# bancada_hx711.net
KiCad netlist of a schematic drawn in EAGLE
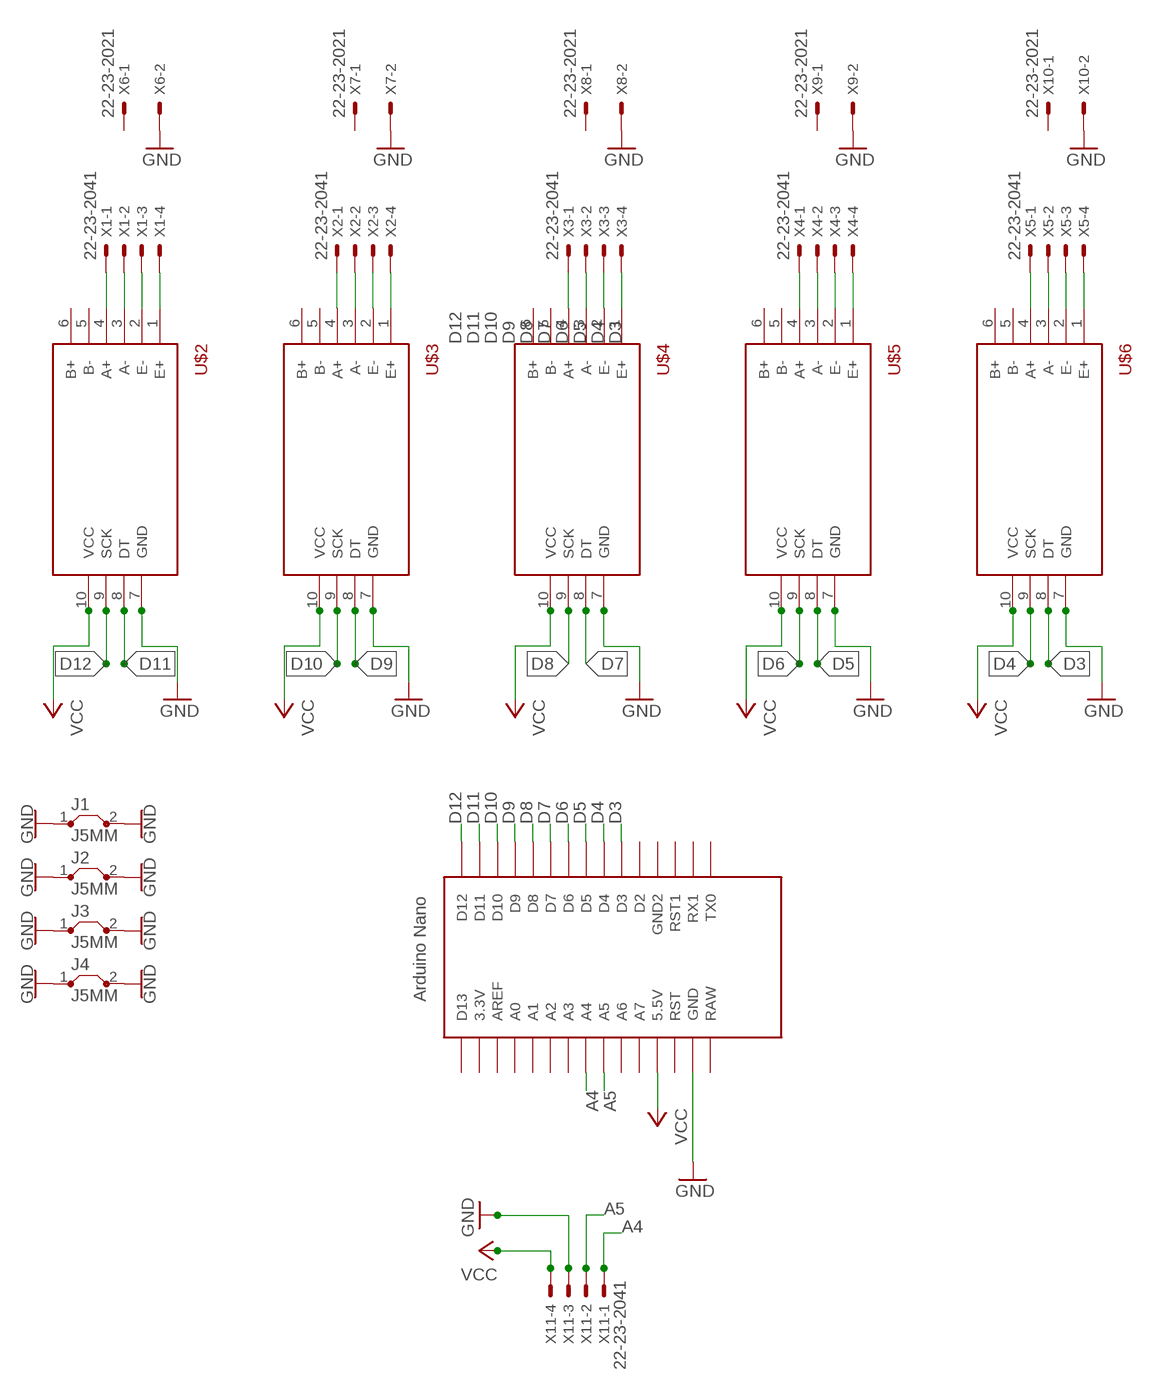
[diagram p0: schematic, sheet 1]

(export (version "E")
  (design (tool "Eeschema 10.0.6"))
  (components
    (comp (ref "J1")
      (value "J5MM")
      (footprint "eagle-import:05")
      (libsource (lib "eagle-import") (part "J5MM"))
    )
    (comp (ref "J2")
      (value "J5MM")
      (footprint "eagle-import:05")
      (libsource (lib "eagle-import") (part "J5MM"))
    )
    (comp (ref "J3")
      (value "J5MM")
      (footprint "eagle-import:05")
      (libsource (lib "eagle-import") (part "J5MM"))
    )
    (comp (ref "J4")
      (value "J5MM")
      (footprint "eagle-import:05")
      (libsource (lib "eagle-import") (part "J5MM"))
    )
    (comp (ref "U$1")
      (value "NANO")
      (footprint "eagle-import:NANO")
      (libsource (lib "eagle-import") (part "NANO"))
    )
    (comp (ref "U$2")
      (value "HX711-1")
      (footprint "eagle-import:HX711-1")
      (libsource (lib "eagle-import") (part "HX711-1"))
    )
    (comp (ref "U$3")
      (value "HX711-1")
      (footprint "eagle-import:HX711-1")
      (libsource (lib "eagle-import") (part "HX711-1"))
    )
    (comp (ref "U$4")
      (value "HX711-1")
      (footprint "eagle-import:HX711-1")
      (libsource (lib "eagle-import") (part "HX711-1"))
    )
    (comp (ref "U$5")
      (value "HX711-1")
      (footprint "eagle-import:HX711-1")
      (libsource (lib "eagle-import") (part "HX711-1"))
    )
    (comp (ref "U$6")
      (value "HX711-1")
      (footprint "eagle-import:HX711-1")
      (libsource (lib "eagle-import") (part "HX711-1"))
    )
    (comp (ref "X1")
      (value "22-23-2041")
      (footprint "eagle-import:22-23-2041")
      (fields (field (name "MF") "MOLEX"))
      (libsource (lib "eagle-import") (part "22-23-2041"))
    )
    (comp (ref "X2")
      (value "22-23-2041")
      (footprint "eagle-import:22-23-2041")
      (fields (field (name "MF") "MOLEX"))
      (libsource (lib "eagle-import") (part "22-23-2041"))
    )
    (comp (ref "X3")
      (value "22-23-2041")
      (footprint "eagle-import:22-23-2041")
      (fields (field (name "MF") "MOLEX"))
      (libsource (lib "eagle-import") (part "22-23-2041"))
    )
    (comp (ref "X4")
      (value "22-23-2041")
      (footprint "eagle-import:22-23-2041")
      (fields (field (name "MF") "MOLEX"))
      (libsource (lib "eagle-import") (part "22-23-2041"))
    )
    (comp (ref "X5")
      (value "22-23-2041")
      (footprint "eagle-import:22-23-2041")
      (fields (field (name "MF") "MOLEX"))
      (libsource (lib "eagle-import") (part "22-23-2041"))
    )
    (comp (ref "X6")
      (value "22-23-2021")
      (footprint "eagle-import:22-23-2021")
      (fields (field (name "MF") "MOLEX"))
      (libsource (lib "eagle-import") (part "22-23-2021"))
    )
    (comp (ref "X7")
      (value "22-23-2021")
      (footprint "eagle-import:22-23-2021")
      (fields (field (name "MF") "MOLEX"))
      (libsource (lib "eagle-import") (part "22-23-2021"))
    )
    (comp (ref "X8")
      (value "22-23-2021")
      (footprint "eagle-import:22-23-2021")
      (fields (field (name "MF") "MOLEX"))
      (libsource (lib "eagle-import") (part "22-23-2021"))
    )
    (comp (ref "X9")
      (value "22-23-2021")
      (footprint "eagle-import:22-23-2021")
      (fields (field (name "MF") "MOLEX"))
      (libsource (lib "eagle-import") (part "22-23-2021"))
    )
    (comp (ref "X10")
      (value "22-23-2021")
      (footprint "eagle-import:22-23-2021")
      (fields (field (name "MF") "MOLEX"))
      (libsource (lib "eagle-import") (part "22-23-2021"))
    )
    (comp (ref "X11")
      (value "22-23-2041")
      (footprint "eagle-import:22-23-2041")
      (fields (field (name "MF") "MOLEX"))
      (libsource (lib "eagle-import") (part "22-23-2041"))
    )
  )
  (nets
    (net (code "1") (name "/A4") (class "Default")
      (node (ref "U$1") (pin "A4") (pinfunction "A4_A4") (pintype "bidirectional"))
      (node (ref "X11") (pin "1") (pinfunction "S_1") (pintype "passive"))
    )
    (net (code "2") (name "/A5") (class "Default")
      (node (ref "U$1") (pin "A5") (pinfunction "A5_A5") (pintype "bidirectional"))
      (node (ref "X11") (pin "2") (pinfunction "S_2") (pintype "passive"))
    )
    (net (code "3") (name "D3") (class "Default")
      (node (ref "U$1") (pin "D3") (pinfunction "D3_D3") (pintype "bidirectional"))
      (node (ref "U$6") (pin "8") (pinfunction "DT_8") (pintype "bidirectional"))
    )
    (net (code "4") (name "D4") (class "Default")
      (node (ref "U$1") (pin "D4") (pinfunction "D4_D4") (pintype "bidirectional"))
      (node (ref "U$6") (pin "9") (pinfunction "SCK_9") (pintype "bidirectional"))
    )
    (net (code "5") (name "D5") (class "Default")
      (node (ref "U$1") (pin "D5") (pinfunction "D5_D5") (pintype "bidirectional"))
      (node (ref "U$5") (pin "8") (pinfunction "DT_8") (pintype "bidirectional"))
    )
    (net (code "6") (name "D6") (class "Default")
      (node (ref "U$1") (pin "D6") (pinfunction "D6_D6") (pintype "bidirectional"))
      (node (ref "U$5") (pin "9") (pinfunction "SCK_9") (pintype "bidirectional"))
    )
    (net (code "7") (name "D7") (class "Default")
      (node (ref "U$1") (pin "D7") (pinfunction "D7_D7") (pintype "bidirectional"))
      (node (ref "U$4") (pin "8") (pinfunction "DT_8") (pintype "bidirectional"))
    )
    (net (code "8") (name "D8") (class "Default")
      (node (ref "U$1") (pin "D8") (pinfunction "D8_D8") (pintype "bidirectional"))
      (node (ref "U$4") (pin "9") (pinfunction "SCK_9") (pintype "bidirectional"))
    )
    (net (code "9") (name "D9") (class "Default")
      (node (ref "U$1") (pin "D9") (pinfunction "D9_D9") (pintype "bidirectional"))
      (node (ref "U$3") (pin "8") (pinfunction "DT_8") (pintype "bidirectional"))
    )
    (net (code "10") (name "D10") (class "Default")
      (node (ref "U$1") (pin "D10") (pinfunction "D10_D10") (pintype "bidirectional"))
      (node (ref "U$3") (pin "9") (pinfunction "SCK_9") (pintype "bidirectional"))
    )
    (net (code "11") (name "D11") (class "Default")
      (node (ref "U$1") (pin "D11") (pinfunction "D11_D11") (pintype "bidirectional"))
      (node (ref "U$2") (pin "8") (pinfunction "DT_8") (pintype "bidirectional"))
    )
    (net (code "12") (name "D12") (class "Default")
      (node (ref "U$1") (pin "D12") (pinfunction "D12_D12") (pintype "bidirectional"))
      (node (ref "U$2") (pin "9") (pinfunction "SCK_9") (pintype "bidirectional"))
    )
    (net (code "13") (name "GND") (class "Default")
      (node (ref "J1") (pin "1") (pinfunction "1_1") (pintype "passive"))
      (node (ref "J1") (pin "2") (pinfunction "2_2") (pintype "passive"))
      (node (ref "J2") (pin "1") (pinfunction "1_1") (pintype "passive"))
      (node (ref "J2") (pin "2") (pinfunction "2_2") (pintype "passive"))
      (node (ref "J3") (pin "1") (pinfunction "1_1") (pintype "passive"))
      (node (ref "J3") (pin "2") (pinfunction "2_2") (pintype "passive"))
      (node (ref "J4") (pin "1") (pinfunction "1_1") (pintype "passive"))
      (node (ref "J4") (pin "2") (pinfunction "2_2") (pintype "passive"))
      (node (ref "U$1") (pin "GND") (pinfunction "GND_GND") (pintype "bidirectional"))
      (node (ref "U$2") (pin "7") (pinfunction "GND_7") (pintype "bidirectional"))
      (node (ref "U$3") (pin "7") (pinfunction "GND_7") (pintype "bidirectional"))
      (node (ref "U$4") (pin "7") (pinfunction "GND_7") (pintype "bidirectional"))
      (node (ref "U$5") (pin "7") (pinfunction "GND_7") (pintype "bidirectional"))
      (node (ref "U$6") (pin "7") (pinfunction "GND_7") (pintype "bidirectional"))
      (node (ref "X10") (pin "2") (pinfunction "S_2") (pintype "passive"))
      (node (ref "X11") (pin "3") (pinfunction "S_3") (pintype "passive"))
      (node (ref "X6") (pin "2") (pinfunction "S_2") (pintype "passive"))
      (node (ref "X7") (pin "2") (pinfunction "S_2") (pintype "passive"))
      (node (ref "X8") (pin "2") (pinfunction "S_2") (pintype "passive"))
      (node (ref "X9") (pin "2") (pinfunction "S_2") (pintype "passive"))
    )
    (net (code "14") (name "Net-(U$2-A+)") (class "Default")
      (node (ref "U$2") (pin "4") (pinfunction "A+_4") (pintype "bidirectional"))
      (node (ref "X1") (pin "1") (pinfunction "S_1") (pintype "passive"))
    )
    (net (code "15") (name "Net-(U$2-A-)") (class "Default")
      (node (ref "U$2") (pin "3") (pinfunction "A-_3") (pintype "bidirectional"))
      (node (ref "X1") (pin "2") (pinfunction "S_2") (pintype "passive"))
    )
    (net (code "16") (name "Net-(U$2-E+)") (class "Default")
      (node (ref "U$2") (pin "1") (pinfunction "E+_1") (pintype "bidirectional"))
      (node (ref "X1") (pin "4") (pinfunction "S_4") (pintype "passive"))
    )
    (net (code "17") (name "Net-(U$2-E-)") (class "Default")
      (node (ref "U$2") (pin "2") (pinfunction "E-_2") (pintype "bidirectional"))
      (node (ref "X1") (pin "3") (pinfunction "S_3") (pintype "passive"))
    )
    (net (code "18") (name "Net-(U$3-A+)") (class "Default")
      (node (ref "U$3") (pin "4") (pinfunction "A+_4") (pintype "bidirectional"))
      (node (ref "X2") (pin "1") (pinfunction "S_1") (pintype "passive"))
    )
    (net (code "19") (name "Net-(U$3-A-)") (class "Default")
      (node (ref "U$3") (pin "3") (pinfunction "A-_3") (pintype "bidirectional"))
      (node (ref "X2") (pin "2") (pinfunction "S_2") (pintype "passive"))
    )
    (net (code "20") (name "Net-(U$3-E+)") (class "Default")
      (node (ref "U$3") (pin "1") (pinfunction "E+_1") (pintype "bidirectional"))
      (node (ref "X2") (pin "4") (pinfunction "S_4") (pintype "passive"))
    )
    (net (code "21") (name "Net-(U$3-E-)") (class "Default")
      (node (ref "U$3") (pin "2") (pinfunction "E-_2") (pintype "bidirectional"))
      (node (ref "X2") (pin "3") (pinfunction "S_3") (pintype "passive"))
    )
    (net (code "22") (name "Net-(U$4-A+)") (class "Default")
      (node (ref "U$4") (pin "4") (pinfunction "A+_4") (pintype "bidirectional"))
      (node (ref "X3") (pin "1") (pinfunction "S_1") (pintype "passive"))
    )
    (net (code "23") (name "Net-(U$4-A-)") (class "Default")
      (node (ref "U$4") (pin "3") (pinfunction "A-_3") (pintype "bidirectional"))
      (node (ref "X3") (pin "2") (pinfunction "S_2") (pintype "passive"))
    )
    (net (code "24") (name "Net-(U$4-E+)") (class "Default")
      (node (ref "U$4") (pin "1") (pinfunction "E+_1") (pintype "bidirectional"))
      (node (ref "X3") (pin "4") (pinfunction "S_4") (pintype "passive"))
    )
    (net (code "25") (name "Net-(U$4-E-)") (class "Default")
      (node (ref "U$4") (pin "2") (pinfunction "E-_2") (pintype "bidirectional"))
      (node (ref "X3") (pin "3") (pinfunction "S_3") (pintype "passive"))
    )
    (net (code "26") (name "Net-(U$5-A+)") (class "Default")
      (node (ref "U$5") (pin "4") (pinfunction "A+_4") (pintype "bidirectional"))
      (node (ref "X4") (pin "1") (pinfunction "S_1") (pintype "passive"))
    )
    (net (code "27") (name "Net-(U$5-A-)") (class "Default")
      (node (ref "U$5") (pin "3") (pinfunction "A-_3") (pintype "bidirectional"))
      (node (ref "X4") (pin "2") (pinfunction "S_2") (pintype "passive"))
    )
    (net (code "28") (name "Net-(U$5-E+)") (class "Default")
      (node (ref "U$5") (pin "1") (pinfunction "E+_1") (pintype "bidirectional"))
      (node (ref "X4") (pin "4") (pinfunction "S_4") (pintype "passive"))
    )
    (net (code "29") (name "Net-(U$5-E-)") (class "Default")
      (node (ref "U$5") (pin "2") (pinfunction "E-_2") (pintype "bidirectional"))
      (node (ref "X4") (pin "3") (pinfunction "S_3") (pintype "passive"))
    )
    (net (code "30") (name "Net-(U$6-A+)") (class "Default")
      (node (ref "U$6") (pin "4") (pinfunction "A+_4") (pintype "bidirectional"))
      (node (ref "X5") (pin "1") (pinfunction "S_1") (pintype "passive"))
    )
    (net (code "31") (name "Net-(U$6-A-)") (class "Default")
      (node (ref "U$6") (pin "3") (pinfunction "A-_3") (pintype "bidirectional"))
      (node (ref "X5") (pin "2") (pinfunction "S_2") (pintype "passive"))
    )
    (net (code "32") (name "Net-(U$6-E+)") (class "Default")
      (node (ref "U$6") (pin "1") (pinfunction "E+_1") (pintype "bidirectional"))
      (node (ref "X5") (pin "4") (pinfunction "S_4") (pintype "passive"))
    )
    (net (code "33") (name "Net-(U$6-E-)") (class "Default")
      (node (ref "U$6") (pin "2") (pinfunction "E-_2") (pintype "bidirectional"))
      (node (ref "X5") (pin "3") (pinfunction "S_3") (pintype "passive"))
    )
    (net (code "34") (name "VCC") (class "Default")
      (node (ref "U$1") (pin "5V") (pinfunction "5.5V_5V") (pintype "bidirectional"))
      (node (ref "U$2") (pin "10") (pinfunction "VCC_10") (pintype "bidirectional"))
      (node (ref "U$3") (pin "10") (pinfunction "VCC_10") (pintype "bidirectional"))
      (node (ref "U$4") (pin "10") (pinfunction "VCC_10") (pintype "bidirectional"))
      (node (ref "U$5") (pin "10") (pinfunction "VCC_10") (pintype "bidirectional"))
      (node (ref "U$6") (pin "10") (pinfunction "VCC_10") (pintype "bidirectional"))
      (node (ref "X11") (pin "4") (pinfunction "S_4") (pintype "passive"))
    )
    (net (code "35") (name "unconnected-(U$1-GND2-PadGND1)") (class "Default")
      (node (ref "U$1") (pin "GND1") (pinfunction "GND2_GND1") (pintype "bidirectional"))
    )
    (net (code "36") (name "unconnected-(U$1-Pad3.3V)") (class "Default")
      (node (ref "U$1") (pin "3.3V") (pinfunction "3.3V_3.3V") (pintype "bidirectional"))
    )
    (net (code "37") (name "unconnected-(U$1-PadA0)") (class "Default")
      (node (ref "U$1") (pin "A0") (pinfunction "A0_A0") (pintype "bidirectional"))
    )
    (net (code "38") (name "unconnected-(U$1-PadA1)") (class "Default")
      (node (ref "U$1") (pin "A1") (pinfunction "A1_A1") (pintype "bidirectional"))
    )
    (net (code "39") (name "unconnected-(U$1-PadA2)") (class "Default")
      (node (ref "U$1") (pin "A2") (pinfunction "A2_A2") (pintype "bidirectional"))
    )
    (net (code "40") (name "unconnected-(U$1-PadA3)") (class "Default")
      (node (ref "U$1") (pin "A3") (pinfunction "A3_A3") (pintype "bidirectional"))
    )
    (net (code "41") (name "unconnected-(U$1-PadA6)") (class "Default")
      (node (ref "U$1") (pin "A6") (pinfunction "A6_A6") (pintype "bidirectional"))
    )
    (net (code "42") (name "unconnected-(U$1-PadA7)") (class "Default")
      (node (ref "U$1") (pin "A7") (pinfunction "A7_A7") (pintype "bidirectional"))
    )
    (net (code "43") (name "unconnected-(U$1-PadAREF)") (class "Default")
      (node (ref "U$1") (pin "AREF") (pinfunction "AREF_AREF") (pintype "bidirectional"))
    )
    (net (code "44") (name "unconnected-(U$1-PadD2)") (class "Default")
      (node (ref "U$1") (pin "D2") (pinfunction "D2_D2") (pintype "bidirectional"))
    )
    (net (code "45") (name "unconnected-(U$1-PadD13)") (class "Default")
      (node (ref "U$1") (pin "D13") (pinfunction "D13_D13") (pintype "bidirectional"))
    )
    (net (code "46") (name "unconnected-(U$1-PadICSP1)") (class "Default")
      (node (ref "U$1") (pin "ICSP1") (pinfunction "ICSP1_ICSP1") (pintype "bidirectional"))
    )
    (net (code "47") (name "unconnected-(U$1-PadICSP2)") (class "Default")
      (node (ref "U$1") (pin "ICSP2") (pinfunction "ICSP2_ICSP2") (pintype "bidirectional"))
    )
    (net (code "48") (name "unconnected-(U$1-PadICSP3)") (class "Default")
      (node (ref "U$1") (pin "ICSP3") (pinfunction "ICSP3_ICSP3") (pintype "bidirectional"))
    )
    (net (code "49") (name "unconnected-(U$1-PadICSP4)") (class "Default")
      (node (ref "U$1") (pin "ICSP4") (pinfunction "ICSP4_ICSP4") (pintype "bidirectional"))
    )
    (net (code "50") (name "unconnected-(U$1-PadICSP5)") (class "Default")
      (node (ref "U$1") (pin "ICSP5") (pinfunction "ICSP5_ICSP5") (pintype "bidirectional"))
    )
    (net (code "51") (name "unconnected-(U$1-PadICSP6)") (class "Default")
      (node (ref "U$1") (pin "ICSP6") (pinfunction "ICSP6_ICSP6") (pintype "bidirectional"))
    )
    (net (code "52") (name "unconnected-(U$1-PadRAW)") (class "Default")
      (node (ref "U$1") (pin "RAW") (pinfunction "RAW_RAW") (pintype "bidirectional"))
    )
    (net (code "53") (name "unconnected-(U$1-PadRST)") (class "Default")
      (node (ref "U$1") (pin "RST") (pinfunction "RST_RST") (pintype "bidirectional"))
    )
    (net (code "54") (name "unconnected-(U$1-PadRST1)") (class "Default")
      (node (ref "U$1") (pin "RST1") (pinfunction "RST1_RST1") (pintype "bidirectional"))
    )
    (net (code "55") (name "unconnected-(U$1-PadRX1)") (class "Default")
      (node (ref "U$1") (pin "RX1") (pinfunction "RX1_RX1") (pintype "bidirectional"))
    )
    (net (code "56") (name "unconnected-(U$1-PadTX0)") (class "Default")
      (node (ref "U$1") (pin "TX0") (pinfunction "TX0_TX0") (pintype "bidirectional"))
    )
    (net (code "57") (name "unconnected-(U$2-B+-Pad6)") (class "Default")
      (node (ref "U$2") (pin "6") (pinfunction "B+_6") (pintype "bidirectional"))
    )
    (net (code "58") (name "unconnected-(U$2-B--Pad5)") (class "Default")
      (node (ref "U$2") (pin "5") (pinfunction "B-_5") (pintype "bidirectional"))
    )
    (net (code "59") (name "unconnected-(U$3-B+-Pad6)") (class "Default")
      (node (ref "U$3") (pin "6") (pinfunction "B+_6") (pintype "bidirectional"))
    )
    (net (code "60") (name "unconnected-(U$3-B--Pad5)") (class "Default")
      (node (ref "U$3") (pin "5") (pinfunction "B-_5") (pintype "bidirectional"))
    )
    (net (code "61") (name "unconnected-(U$4-B+-Pad6)") (class "Default")
      (node (ref "U$4") (pin "6") (pinfunction "B+_6") (pintype "bidirectional"))
    )
    (net (code "62") (name "unconnected-(U$4-B--Pad5)") (class "Default")
      (node (ref "U$4") (pin "5") (pinfunction "B-_5") (pintype "bidirectional"))
    )
    (net (code "63") (name "unconnected-(U$5-B+-Pad6)") (class "Default")
      (node (ref "U$5") (pin "6") (pinfunction "B+_6") (pintype "bidirectional"))
    )
    (net (code "64") (name "unconnected-(U$5-B--Pad5)") (class "Default")
      (node (ref "U$5") (pin "5") (pinfunction "B-_5") (pintype "bidirectional"))
    )
    (net (code "65") (name "unconnected-(U$6-B+-Pad6)") (class "Default")
      (node (ref "U$6") (pin "6") (pinfunction "B+_6") (pintype "bidirectional"))
    )
    (net (code "66") (name "unconnected-(U$6-B--Pad5)") (class "Default")
      (node (ref "U$6") (pin "5") (pinfunction "B-_5") (pintype "bidirectional"))
    )
    (net (code "67") (name "unconnected-(X6A-S-Pad1)") (class "Default")
      (node (ref "X6") (pin "1") (pinfunction "S_1") (pintype "passive"))
    )
    (net (code "68") (name "unconnected-(X7A-S-Pad1)") (class "Default")
      (node (ref "X7") (pin "1") (pinfunction "S_1") (pintype "passive"))
    )
    (net (code "69") (name "unconnected-(X8A-S-Pad1)") (class "Default")
      (node (ref "X8") (pin "1") (pinfunction "S_1") (pintype "passive"))
    )
    (net (code "70") (name "unconnected-(X9A-S-Pad1)") (class "Default")
      (node (ref "X9") (pin "1") (pinfunction "S_1") (pintype "passive"))
    )
    (net (code "71") (name "unconnected-(X10A-S-Pad1)") (class "Default")
      (node (ref "X10") (pin "1") (pinfunction "S_1") (pintype "passive"))
    )
  )
)
